# HackmodWear.net
KiCad netlist of a schematic drawn in EAGLE
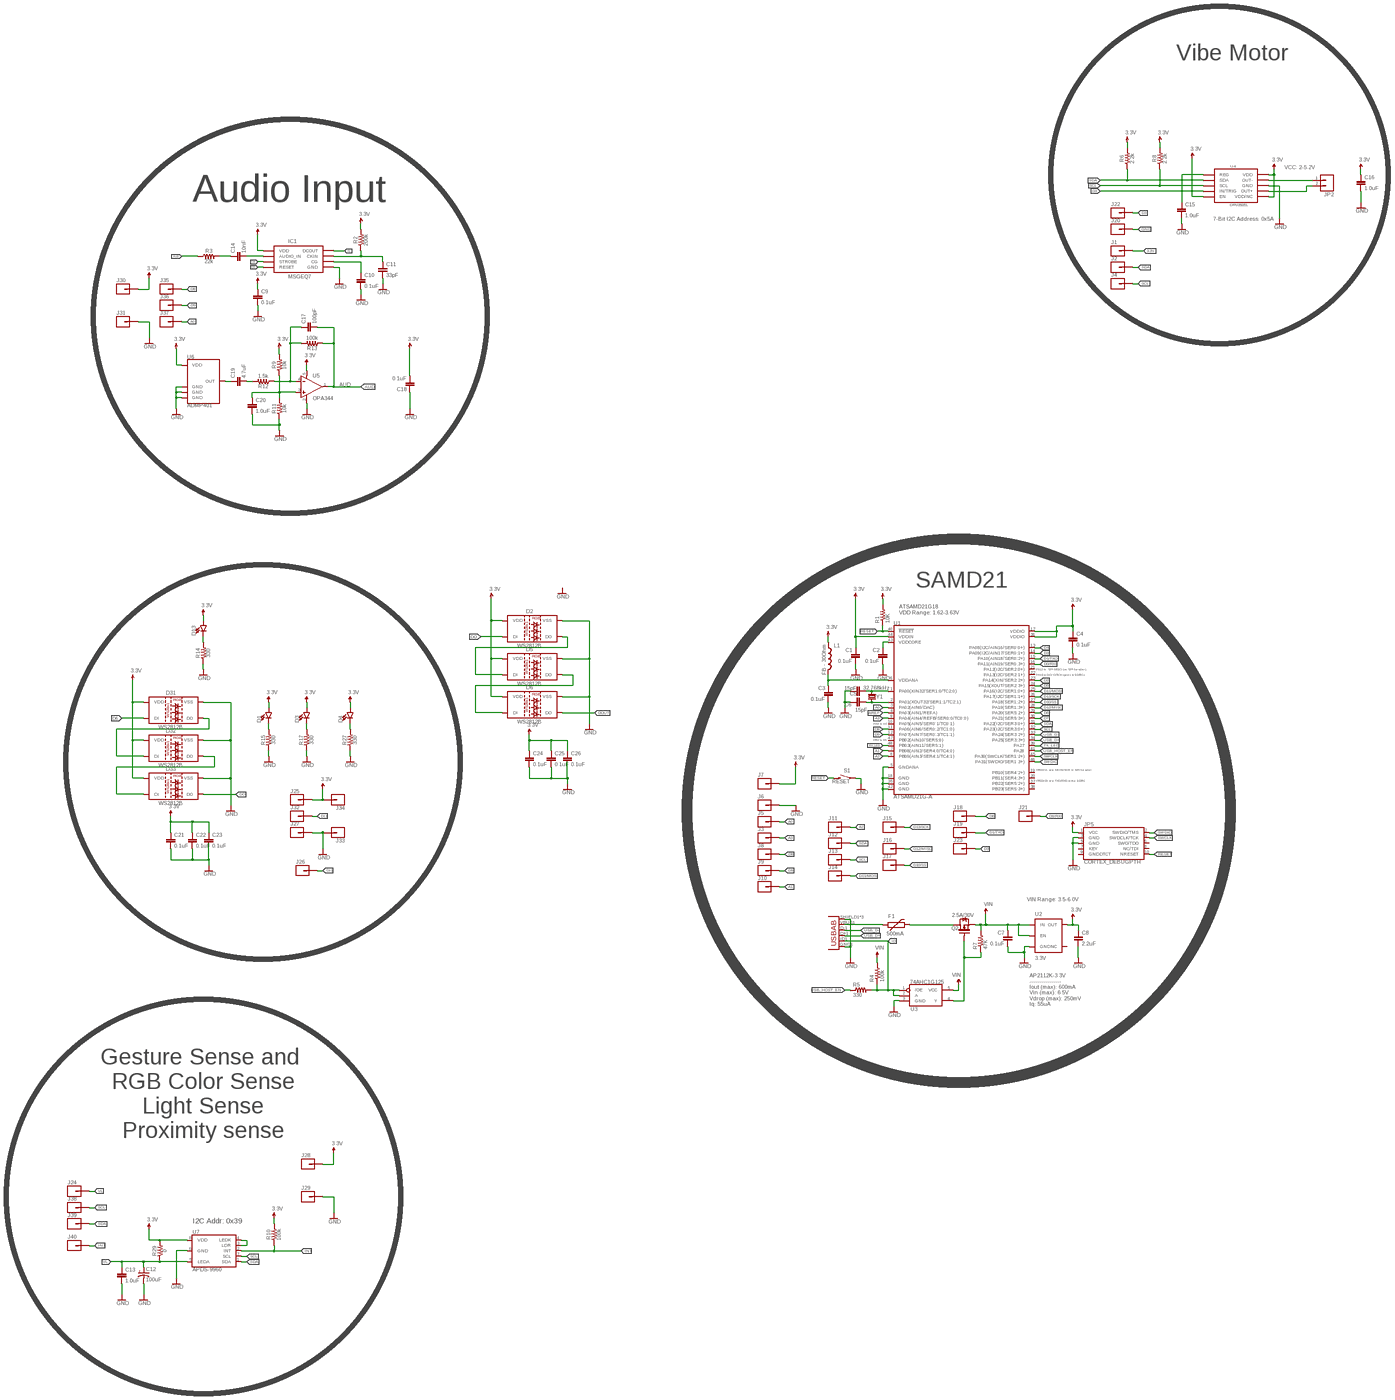
[diagram p0: schematic, sheet 1, overview]
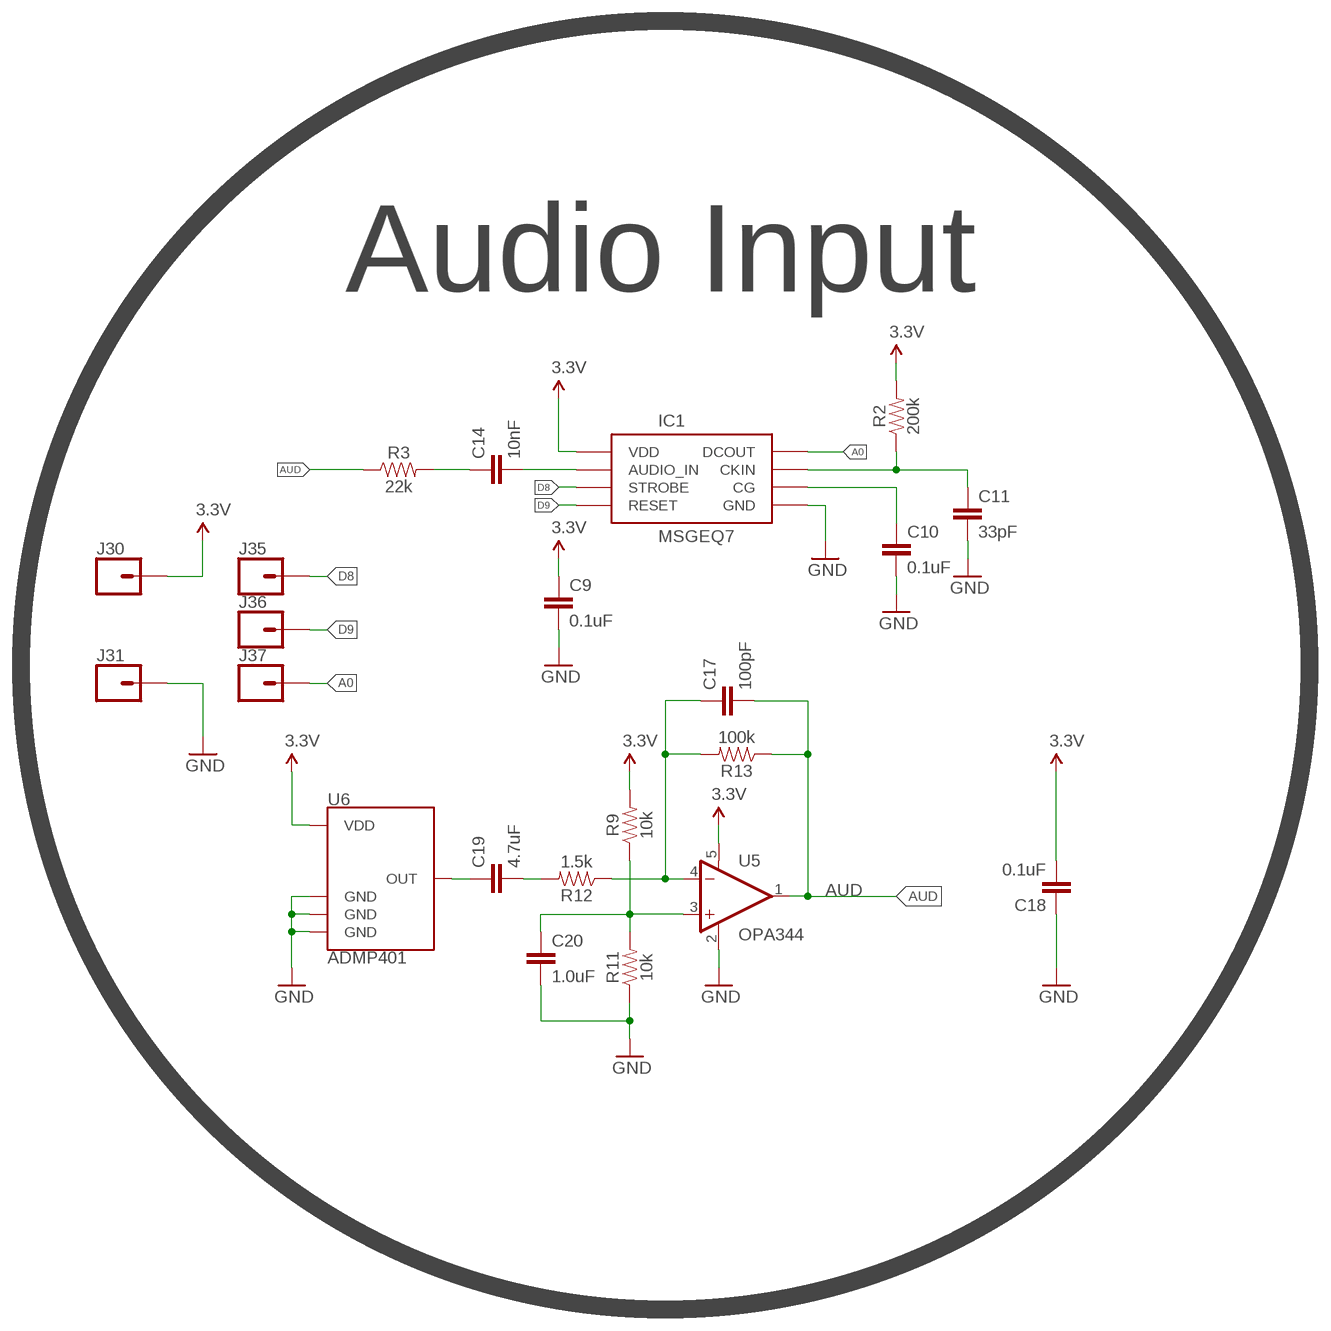
[diagram p1: schematic, sheet 1, part 1 of 4]
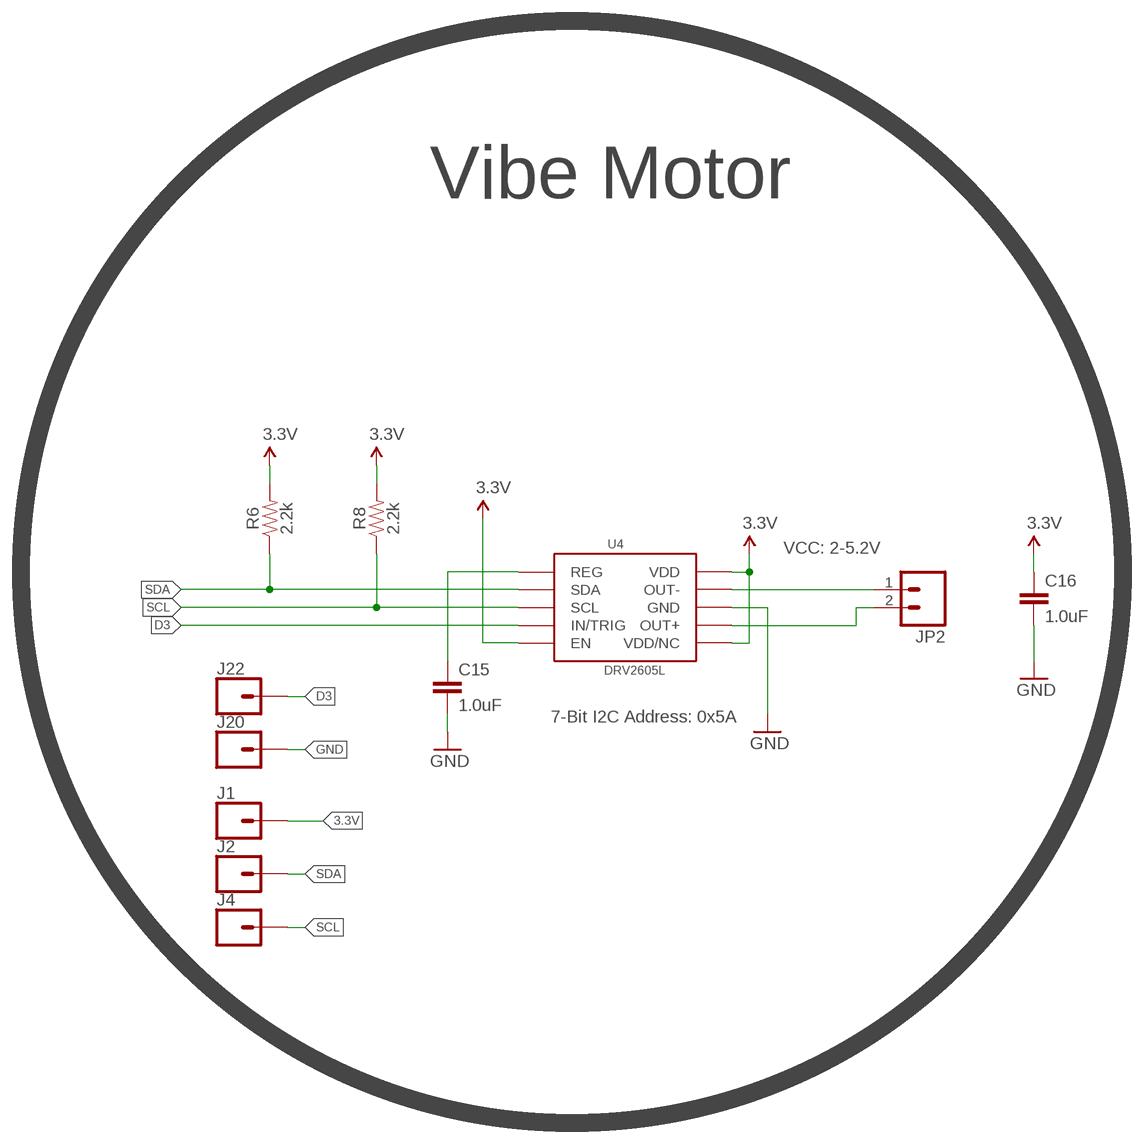
[diagram p2: schematic, sheet 1, part 2 of 4]
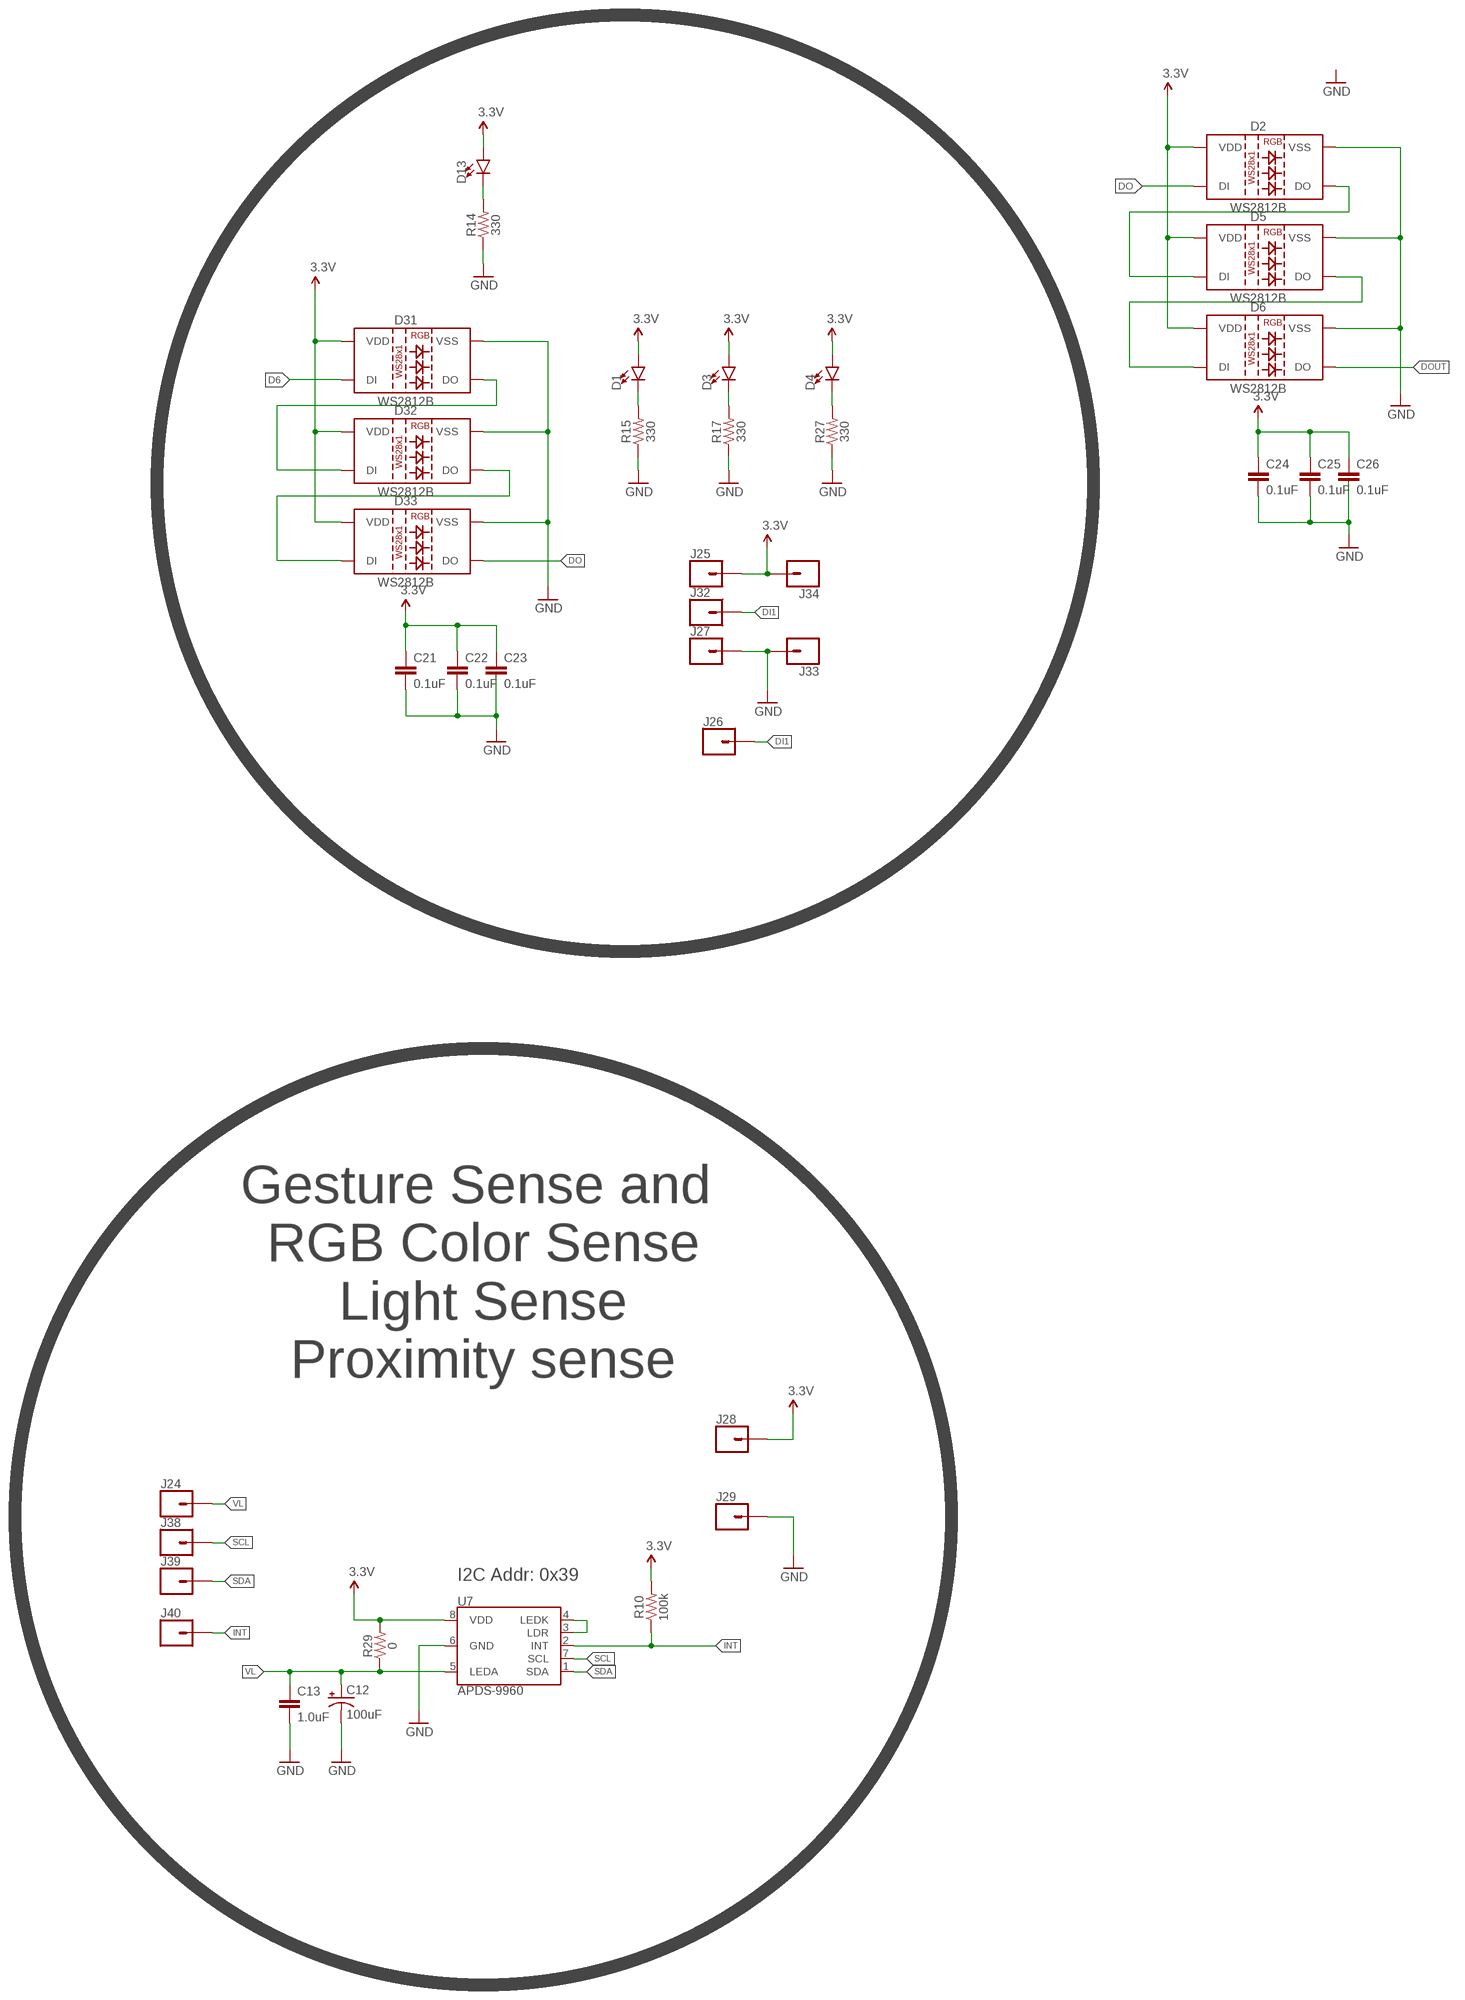
[diagram p3: schematic, sheet 1, part 3 of 4]
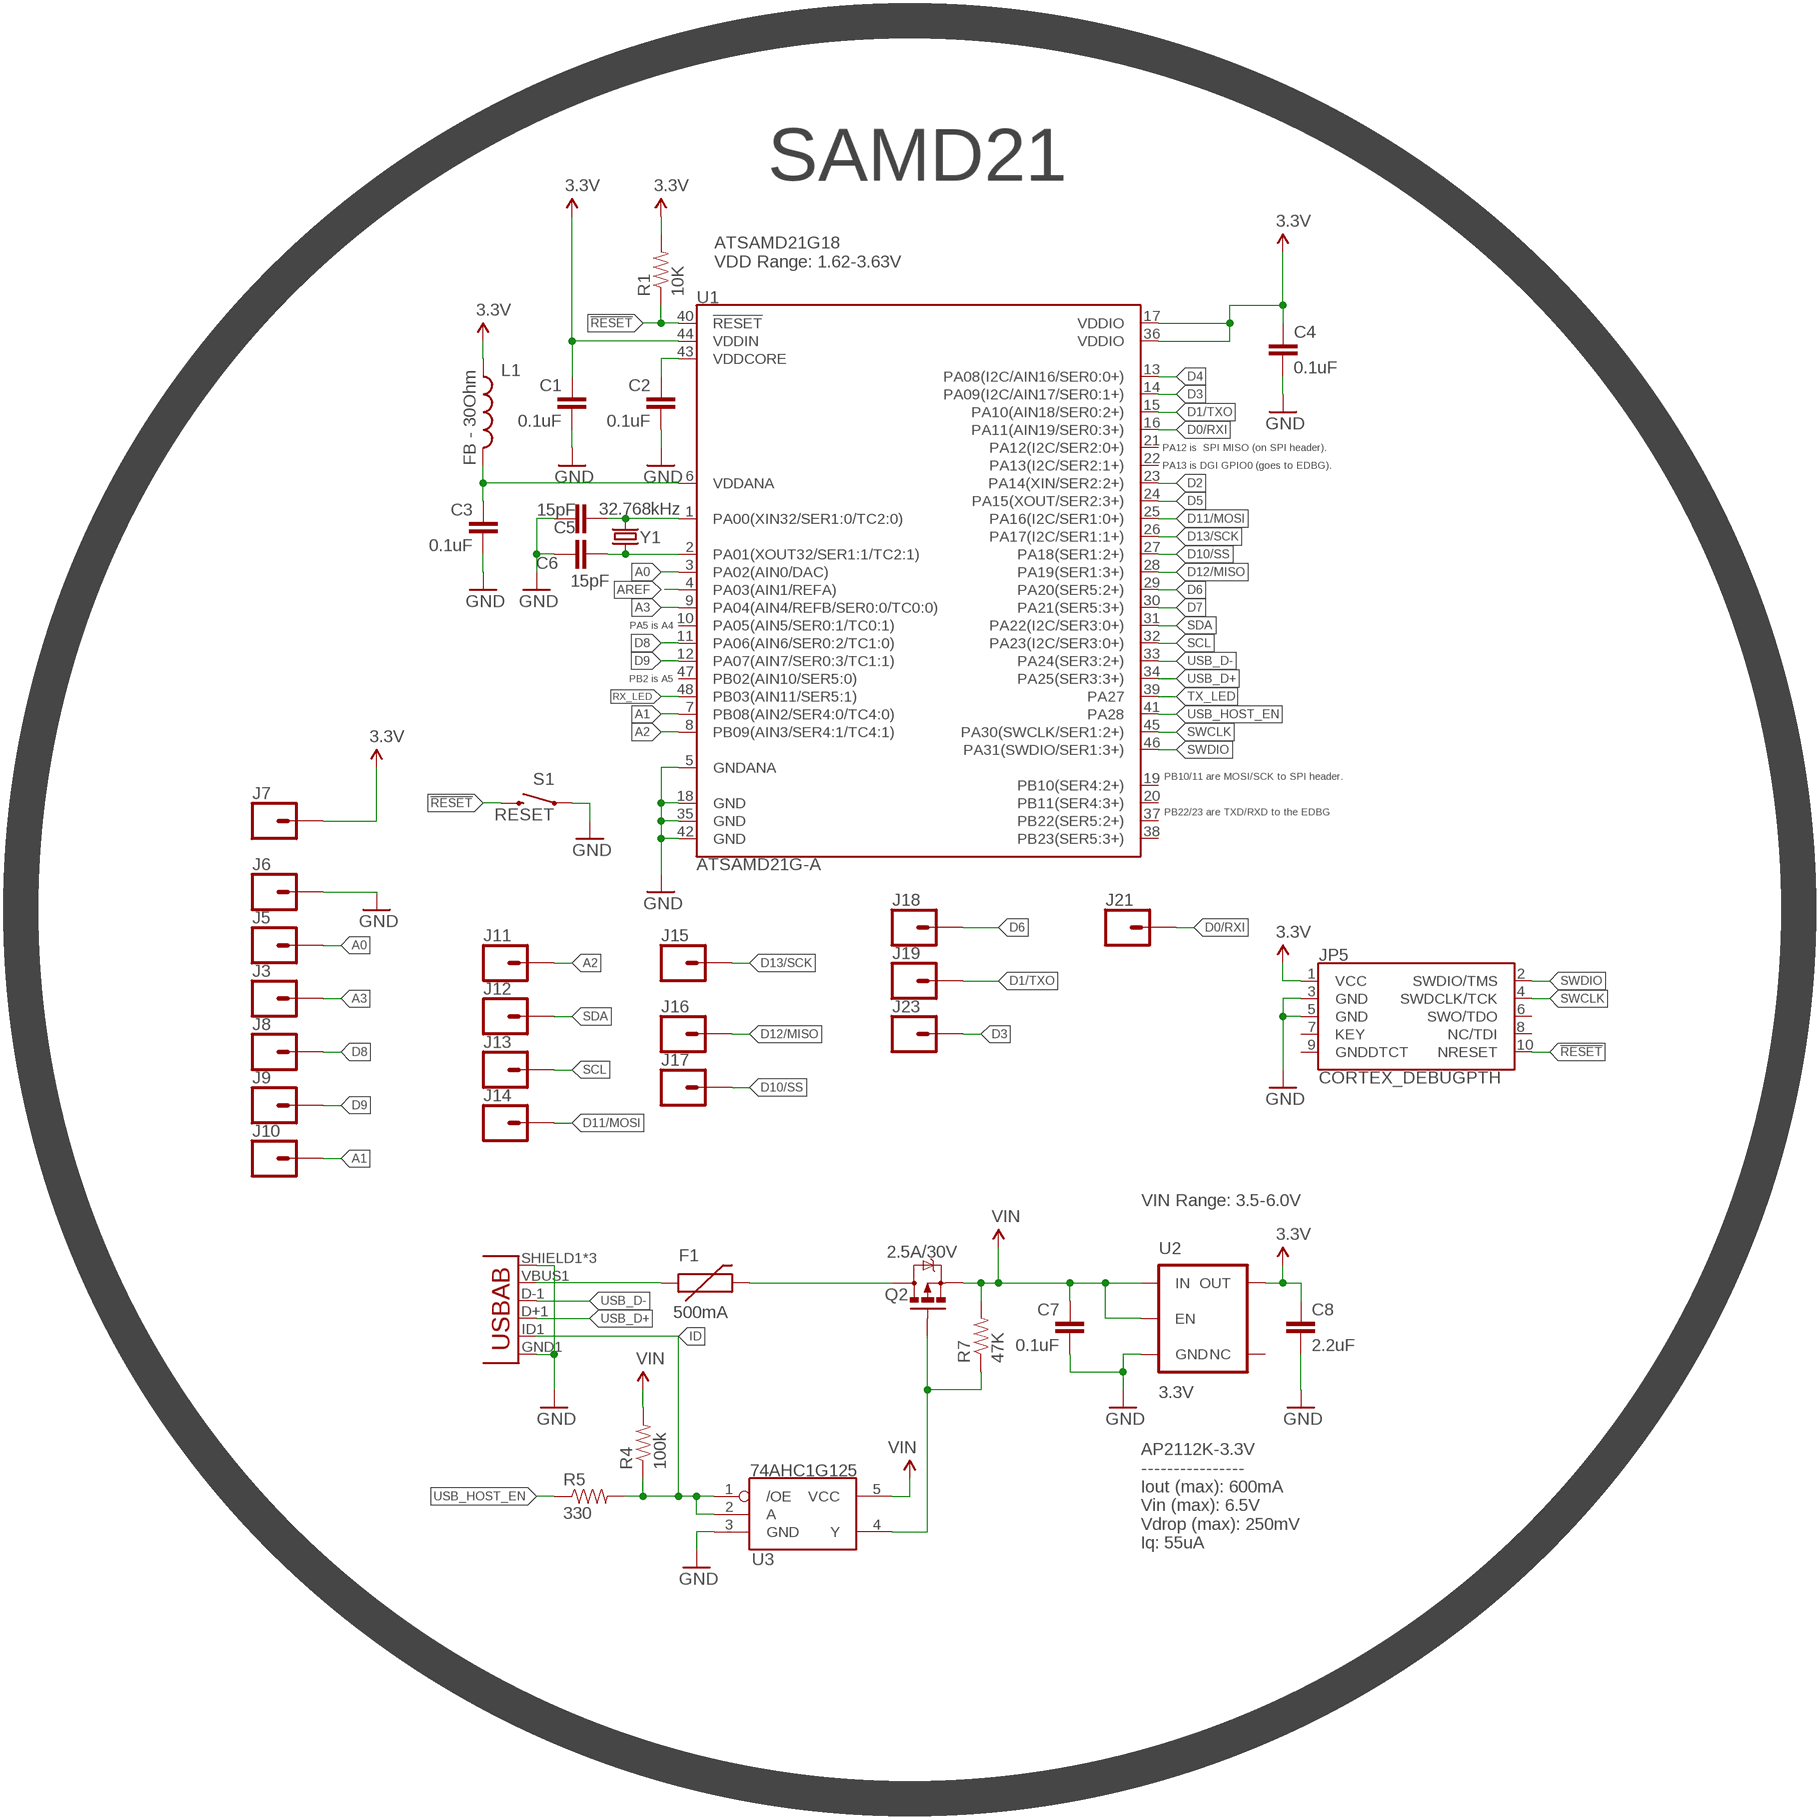
[diagram p4: schematic, sheet 1, part 4 of 4]

(export (version "E")
  (design (tool "Eeschema 10.0.6"))
  (components
    (comp (ref "C1")
      (value "0.1uF")
      (footprint "eagle-import:0603")
      (libsource (lib "eagle-import") (part "0.1UF-0603-25V-(+80/-20%)"))
    )
    (comp (ref "C2")
      (value "0.1uF")
      (footprint "eagle-import:0603")
      (libsource (lib "eagle-import") (part "0.1UF-0603-25V-(+80/-20%)"))
    )
    (comp (ref "C3")
      (value "0.1uF")
      (footprint "eagle-import:0603")
      (libsource (lib "eagle-import") (part "0.1UF-0603-25V-(+80/-20%)"))
    )
    (comp (ref "C4")
      (value "0.1uF")
      (footprint "eagle-import:0603")
      (libsource (lib "eagle-import") (part "0.1UF-0603-25V-(+80/-20%)"))
    )
    (comp (ref "C5")
      (value "15pF")
      (footprint "eagle-import:0603")
      (libsource (lib "eagle-import") (part "15PF-0603-50V-5%"))
    )
    (comp (ref "C6")
      (value "15pF")
      (footprint "eagle-import:0603")
      (libsource (lib "eagle-import") (part "15PF-0603-50V-5%"))
    )
    (comp (ref "C7")
      (value "0.1uF")
      (footprint "eagle-import:0603")
      (libsource (lib "eagle-import") (part "0.1UF-0603-25V-(+80/-20%)"))
    )
    (comp (ref "C8")
      (value "2.2uF")
      (footprint "eagle-import:0603-CAP")
      (libsource (lib "eagle-import") (part "2.2UF-10V-20%(0603)"))
    )
    (comp (ref "C9")
      (value "0.1uF")
      (footprint "eagle-import:0603")
      (libsource (lib "eagle-import") (part "0.1UF-0603-25V-(+80/-20%)"))
    )
    (comp (ref "C10")
      (value "0.1uF")
      (footprint "eagle-import:0603")
      (libsource (lib "eagle-import") (part "0.1UF-0603-25V-(+80/-20%)"))
    )
    (comp (ref "C11")
      (value "33pF")
      (footprint "eagle-import:0603")
      (libsource (lib "eagle-import") (part "33PF-0603-50V-5%"))
    )
    (comp (ref "C12")
      (value "100uF")
      (footprint "eagle-import:EIA7343")
      (libsource (lib "eagle-import") (part "100UF-POLAR-EIA7343-10V-10%(TANT)"))
    )
    (comp (ref "C13")
      (value "1.0uF")
      (footprint "eagle-import:0603")
      (libsource (lib "eagle-import") (part "1.0UF-0603-16V-10%"))
    )
    (comp (ref "C14")
      (value "10nF")
      (footprint "eagle-import:0603")
      (libsource (lib "eagle-import") (part "10NF-0603-50V-10%"))
    )
    (comp (ref "C15")
      (value "1.0uF")
      (footprint "eagle-import:0402-CAP")
      (libsource (lib "eagle-import") (part "1.0UF-16V-10%(0402)"))
    )
    (comp (ref "C16")
      (value "1.0uF")
      (footprint "eagle-import:0402-CAP")
      (libsource (lib "eagle-import") (part "1.0UF-16V-10%(0402)"))
    )
    (comp (ref "C17")
      (value "100pF")
      (footprint "eagle-import:0603")
      (libsource (lib "eagle-import") (part "100PF-0603-50V-5%"))
    )
    (comp (ref "C18")
      (value "0.1uF")
      (footprint "eagle-import:0603")
      (libsource (lib "eagle-import") (part "0.1UF-0603-25V-(+80/-20%)"))
    )
    (comp (ref "C19")
      (value "4.7uF")
      (footprint "eagle-import:0603")
      (libsource (lib "eagle-import") (part "4.7UF0603"))
    )
    (comp (ref "C20")
      (value "1.0uF")
      (footprint "eagle-import:0603")
      (libsource (lib "eagle-import") (part "1.0UF-0603-16V-10%"))
    )
    (comp (ref "C21")
      (value "0.1uF")
      (footprint "eagle-import:0603")
      (libsource (lib "eagle-import") (part "0.1UF-0603-25V-(+80/-20%)"))
    )
    (comp (ref "C22")
      (value "0.1uF")
      (footprint "eagle-import:0603")
      (libsource (lib "eagle-import") (part "0.1UF-0603-25V-(+80/-20%)"))
    )
    (comp (ref "C23")
      (value "0.1uF")
      (footprint "eagle-import:0603")
      (libsource (lib "eagle-import") (part "0.1UF-0603-25V-(+80/-20%)"))
    )
    (comp (ref "C24")
      (value "0.1uF")
      (footprint "eagle-import:0603")
      (libsource (lib "eagle-import") (part "0.1UF-0603-25V-(+80/-20%)"))
    )
    (comp (ref "C25")
      (value "0.1uF")
      (footprint "eagle-import:0603")
      (libsource (lib "eagle-import") (part "0.1UF-0603-25V-(+80/-20%)"))
    )
    (comp (ref "C26")
      (value "0.1uF")
      (footprint "eagle-import:0603")
      (libsource (lib "eagle-import") (part "0.1UF-0603-25V-(+80/-20%)"))
    )
    (comp (ref "D1")
      (value "LED1206")
      (footprint "eagle-import:LED-1206")
      (libsource (lib "eagle-import") (part "LED1206"))
    )
    (comp (ref "D2")
      (value "WS2812B")
      (footprint "eagle-import:WS2812B")
      (libsource (lib "eagle-import") (part "WS2812B"))
    )
    (comp (ref "D3")
      (value "LED1206")
      (footprint "eagle-import:LED-1206")
      (libsource (lib "eagle-import") (part "LED1206"))
    )
    (comp (ref "D4")
      (value "LED1206")
      (footprint "eagle-import:LED-1206")
      (libsource (lib "eagle-import") (part "LED1206"))
    )
    (comp (ref "D5")
      (value "WS2812B")
      (footprint "eagle-import:WS2812B")
      (libsource (lib "eagle-import") (part "WS2812B"))
    )
    (comp (ref "D6")
      (value "WS2812B")
      (footprint "eagle-import:WS2812B")
      (libsource (lib "eagle-import") (part "WS2812B"))
    )
    (comp (ref "D13")
      (value "LED1206")
      (footprint "eagle-import:LED-1206")
      (libsource (lib "eagle-import") (part "LED1206"))
    )
    (comp (ref "D31")
      (value "WS2812B")
      (footprint "eagle-import:WS2812B")
      (libsource (lib "eagle-import") (part "WS2812B"))
    )
    (comp (ref "D32")
      (value "WS2812B")
      (footprint "eagle-import:WS2812B")
      (libsource (lib "eagle-import") (part "WS2812B"))
    )
    (comp (ref "D33")
      (value "WS2812B")
      (footprint "eagle-import:WS2812B")
      (libsource (lib "eagle-import") (part "WS2812B"))
    )
    (comp (ref "F1")
      (value "500mA")
      (footprint "eagle-import:PTC-1206")
      (libsource (lib "eagle-import") (part "PTCSMD"))
    )
    (comp (ref "IC1")
      (value "MSGEQ7N")
      (footprint "eagle-import:SO08")
      (libsource (lib "eagle-import") (part "MSGEQ7SOIC"))
    )
    (comp (ref "J1")
      (value "CONN_01")
      (footprint "eagle-import:1X01")
      (libsource (lib "eagle-import") (part "CONN_01"))
    )
    (comp (ref "J2")
      (value "CONN_01")
      (footprint "eagle-import:1X01")
      (libsource (lib "eagle-import") (part "CONN_01"))
    )
    (comp (ref "J3")
      (value "CONN_01")
      (footprint "eagle-import:1X01")
      (libsource (lib "eagle-import") (part "CONN_01"))
    )
    (comp (ref "J4")
      (value "CONN_01")
      (footprint "eagle-import:1X01")
      (libsource (lib "eagle-import") (part "CONN_01"))
    )
    (comp (ref "J5")
      (value "CONN_01")
      (footprint "eagle-import:1X01")
      (libsource (lib "eagle-import") (part "CONN_01"))
    )
    (comp (ref "J6")
      (value "CONN_01")
      (footprint "eagle-import:1X01")
      (libsource (lib "eagle-import") (part "CONN_01"))
    )
    (comp (ref "J7")
      (value "CONN_01")
      (footprint "eagle-import:1X01")
      (libsource (lib "eagle-import") (part "CONN_01"))
    )
    (comp (ref "J8")
      (value "CONN_01")
      (footprint "eagle-import:1X01")
      (libsource (lib "eagle-import") (part "CONN_01"))
    )
    (comp (ref "J9")
      (value "CONN_01")
      (footprint "eagle-import:1X01")
      (libsource (lib "eagle-import") (part "CONN_01"))
    )
    (comp (ref "J10")
      (value "CONN_01")
      (footprint "eagle-import:1X01")
      (libsource (lib "eagle-import") (part "CONN_01"))
    )
    (comp (ref "J11")
      (value "CONN_01")
      (footprint "eagle-import:1X01")
      (libsource (lib "eagle-import") (part "CONN_01"))
    )
    (comp (ref "J12")
      (value "CONN_01")
      (footprint "eagle-import:1X01")
      (libsource (lib "eagle-import") (part "CONN_01"))
    )
    (comp (ref "J13")
      (value "CONN_01")
      (footprint "eagle-import:1X01")
      (libsource (lib "eagle-import") (part "CONN_01"))
    )
    (comp (ref "J14")
      (value "CONN_01")
      (footprint "eagle-import:1X01")
      (libsource (lib "eagle-import") (part "CONN_01"))
    )
    (comp (ref "J15")
      (value "CONN_01")
      (footprint "eagle-import:1X01")
      (libsource (lib "eagle-import") (part "CONN_01"))
    )
    (comp (ref "J16")
      (value "CONN_01")
      (footprint "eagle-import:1X01")
      (libsource (lib "eagle-import") (part "CONN_01"))
    )
    (comp (ref "J17")
      (value "CONN_01")
      (footprint "eagle-import:1X01")
      (libsource (lib "eagle-import") (part "CONN_01"))
    )
    (comp (ref "J18")
      (value "CONN_01")
      (footprint "eagle-import:1X01")
      (libsource (lib "eagle-import") (part "CONN_01"))
    )
    (comp (ref "J19")
      (value "CONN_01")
      (footprint "eagle-import:1X01")
      (libsource (lib "eagle-import") (part "CONN_01"))
    )
    (comp (ref "J20")
      (value "CONN_01")
      (footprint "eagle-import:1X01")
      (libsource (lib "eagle-import") (part "CONN_01"))
    )
    (comp (ref "J21")
      (value "CONN_01")
      (footprint "eagle-import:1X01")
      (libsource (lib "eagle-import") (part "CONN_01"))
    )
    (comp (ref "J22")
      (value "CONN_01")
      (footprint "eagle-import:1X01")
      (libsource (lib "eagle-import") (part "CONN_01"))
    )
    (comp (ref "J23")
      (value "CONN_01")
      (footprint "eagle-import:1X01")
      (libsource (lib "eagle-import") (part "CONN_01"))
    )
    (comp (ref "J24")
      (value "CONN_01")
      (footprint "eagle-import:1X01")
      (libsource (lib "eagle-import") (part "CONN_01"))
    )
    (comp (ref "J25")
      (value "CONN_01")
      (footprint "eagle-import:1X01")
      (libsource (lib "eagle-import") (part "CONN_01"))
    )
    (comp (ref "J26")
      (value "CONN_01")
      (footprint "eagle-import:1X01")
      (libsource (lib "eagle-import") (part "CONN_01"))
    )
    (comp (ref "J27")
      (value "CONN_01")
      (footprint "eagle-import:1X01")
      (libsource (lib "eagle-import") (part "CONN_01"))
    )
    (comp (ref "J28")
      (value "CONN_01")
      (footprint "eagle-import:1X01")
      (libsource (lib "eagle-import") (part "CONN_01"))
    )
    (comp (ref "J29")
      (value "CONN_01")
      (footprint "eagle-import:1X01")
      (libsource (lib "eagle-import") (part "CONN_01"))
    )
    (comp (ref "J30")
      (value "CONN_01")
      (footprint "eagle-import:1X01")
      (libsource (lib "eagle-import") (part "CONN_01"))
    )
    (comp (ref "J31")
      (value "CONN_01")
      (footprint "eagle-import:1X01")
      (libsource (lib "eagle-import") (part "CONN_01"))
    )
    (comp (ref "J32")
      (value "CONN_01")
      (footprint "eagle-import:1X01")
      (libsource (lib "eagle-import") (part "CONN_01"))
    )
    (comp (ref "J33")
      (value "CONN_01")
      (footprint "eagle-import:1X01")
      (libsource (lib "eagle-import") (part "CONN_01"))
    )
    (comp (ref "J34")
      (value "CONN_01")
      (footprint "eagle-import:1X01")
      (libsource (lib "eagle-import") (part "CONN_01"))
    )
    (comp (ref "J35")
      (value "CONN_01")
      (footprint "eagle-import:1X01")
      (libsource (lib "eagle-import") (part "CONN_01"))
    )
    (comp (ref "J36")
      (value "CONN_01")
      (footprint "eagle-import:1X01")
      (libsource (lib "eagle-import") (part "CONN_01"))
    )
    (comp (ref "J37")
      (value "CONN_01")
      (footprint "eagle-import:1X01")
      (libsource (lib "eagle-import") (part "CONN_01"))
    )
    (comp (ref "J38")
      (value "CONN_01")
      (footprint "eagle-import:1X01")
      (libsource (lib "eagle-import") (part "CONN_01"))
    )
    (comp (ref "J39")
      (value "CONN_01")
      (footprint "eagle-import:1X01")
      (libsource (lib "eagle-import") (part "CONN_01"))
    )
    (comp (ref "J40")
      (value "CONN_01")
      (footprint "eagle-import:1X01")
      (libsource (lib "eagle-import") (part "CONN_01"))
    )
    (comp (ref "JP2")
      (value "M02PTH")
      (footprint "eagle-import:1X02@1")
      (libsource (lib "eagle-import") (part "M02PTH"))
    )
    (comp (ref "JP3")
      (value "USB-ABCONN-11794")
      (footprint "eagle-import:USB-AB-MICRO-SMD_V03")
      (libsource (lib "eagle-import") (part "USB-ABCONN-11794"))
    )
    (comp (ref "JP5")
      (value "CORTEX_DEBUGPTH")
      (footprint "eagle-import:2X5-PTH-1.27MM")
      (libsource (lib "eagle-import") (part "CORTEX_DEBUGPTH"))
    )
    (comp (ref "L1")
      (value "FB - 30Ohm")
      (footprint "eagle-import:0603")
      (libsource (lib "eagle-import") (part "INDUCTOR0603"))
    )
    (comp (ref "Q2")
      (value "2.5A/30V")
      (footprint "eagle-import:SOT23-3")
      (libsource (lib "eagle-import") (part "MOSFET-PCHANNELDMG2307L"))
    )
    (comp (ref "R1")
      (value "10K")
      (footprint "eagle-import:0603-RES@1")
      (libsource (lib "eagle-import") (part "10KOHM-1/10W-1%(0603)0603"))
    )
    (comp (ref "R2")
      (value "200k")
      (footprint "eagle-import:0603")
      (libsource (lib "eagle-import") (part "200KOHM-0603-1/10W-1%"))
    )
    (comp (ref "R3")
      (value "22k")
      (footprint "eagle-import:0603")
      (libsource (lib "eagle-import") (part "22KOHM-0603-1/10W-1%"))
    )
    (comp (ref "R4")
      (value "100k")
      (footprint "eagle-import:0603-RES@1")
      (libsource (lib "eagle-import") (part "100KOHM-1/10W-1%(0603)"))
    )
    (comp (ref "R5")
      (value "330")
      (footprint "eagle-import:0603-RES@1")
      (libsource (lib "eagle-import") (part "330OHM1/10W1%(0603)"))
    )
    (comp (ref "R6")
      (value "2.2k")
      (footprint "eagle-import:0603")
      (libsource (lib "eagle-import") (part "2.2KOHM-0603-1/10W-1%"))
    )
    (comp (ref "R7")
      (value "47K")
      (footprint "eagle-import:0603-RES@1")
      (libsource (lib "eagle-import") (part "47KOHM1/10W1%(0603)"))
    )
    (comp (ref "R8")
      (value "2.2k")
      (footprint "eagle-import:0603")
      (libsource (lib "eagle-import") (part "2.2KOHM-0603-1/10W-1%"))
    )
    (comp (ref "R9")
      (value "10k")
      (footprint "eagle-import:0603")
      (libsource (lib "eagle-import") (part "10KOHM-0603-1/10W-1%"))
    )
    (comp (ref "R10")
      (value "100k")
      (footprint "eagle-import:0603")
      (libsource (lib "eagle-import") (part "100KOHM-0603-1/10W-1%"))
    )
    (comp (ref "R11")
      (value "10k")
      (footprint "eagle-import:0603")
      (libsource (lib "eagle-import") (part "10KOHM-0603-1/10W-1%"))
    )
    (comp (ref "R12")
      (value "1.5k")
      (footprint "eagle-import:0603")
      (libsource (lib "eagle-import") (part "1.5KOHM-0603-1/10W-1%"))
    )
    (comp (ref "R13")
      (value "100k")
      (footprint "eagle-import:0603")
      (libsource (lib "eagle-import") (part "100KOHM-0603-1/10W-1%"))
    )
    (comp (ref "R14")
      (value "330")
      (footprint "eagle-import:0603")
      (libsource (lib "eagle-import") (part "330OHM-0603-1/10W-1%"))
    )
    (comp (ref "R15")
      (value "330")
      (footprint "eagle-import:0603")
      (libsource (lib "eagle-import") (part "330OHM-0603-1/10W-1%"))
    )
    (comp (ref "R17")
      (value "330")
      (footprint "eagle-import:0603")
      (libsource (lib "eagle-import") (part "330OHM-0603-1/10W-1%"))
    )
    (comp (ref "R27")
      (value "330")
      (footprint "eagle-import:0603")
      (libsource (lib "eagle-import") (part "330OHM-0603-1/10W-1%"))
    )
    (comp (ref "R29")
      (value "0")
      (footprint "eagle-import:0603")
      (libsource (lib "eagle-import") (part "0OHM-0603-1/10W-5%"))
    )
    (comp (ref "S1")
      (value "RESET")
      (footprint "eagle-import:TACTILE_SWITCH_SMD_4.6X2.8MM")
      (libsource (lib "eagle-import") (part "SWITCH-MOMENTARY-2SMD-4.6X2.8MM"))
    )
    (comp (ref "U1")
      (value "ATSAMD21G-A")
      (footprint "eagle-import:TQFP-48")
      (libsource (lib "eagle-import") (part "ATSAMD21G-A"))
    )
    (comp (ref "U2")
      (value "3.3V")
      (footprint "eagle-import:SOT23-5")
      (libsource (lib "eagle-import") (part "V_REG_AP2112K-3.3V"))
    )
    (comp (ref "U3")
      (value "74AHC1G125")
      (footprint "eagle-import:SOT23-5")
      (libsource (lib "eagle-import") (part "74AHC1G125"))
    )
    (comp (ref "U4")
      (value "DRV2605L")
      (footprint "eagle-import:VSSOP-10")
      (libsource (lib "eagle-import") (part "DRV2605L"))
    )
    (comp (ref "U5")
      (value "OPA344")
      (footprint "eagle-import:SOT23-5")
      (libsource (lib "eagle-import") (part "OPA344"))
    )
    (comp (ref "U6")
      (value "ADMP401")
      (footprint "eagle-import:ADMP401")
      (libsource (lib "eagle-import") (part "ADMP401"))
    )
    (comp (ref "U7")
      (value "APDS-9960")
      (footprint "eagle-import:APDS-9960")
      (libsource (lib "eagle-import") (part "APDS-9960"))
    )
    (comp (ref "Y1")
      (value "32.768kHz")
      (footprint "eagle-import:CRYSTAL-SMD-3.2X1.5MM")
      (libsource (lib "eagle-import") (part "CRYSTAL3.2X1.5MM"))
    )
  )
  (nets
    (net (code "1") (name "/~{RESET}") (class "Default")
      (node (ref "JP5") (pin "10") (pinfunction "NRESET_10") (pintype "bidirectional"))
      (node (ref "R1") (pin "1") (pinfunction "1_1") (pintype "passive"))
      (node (ref "S1") (pin "3") (pinfunction "2_3") (pintype "passive"))
      (node (ref "S1") (pin "4") (pinfunction "2_4") (pintype "passive"))
      (node (ref "U1") (pin "40") (pinfunction "~{RESET}_40") (pintype "bidirectional"))
    )
    (net (code "2") (name "3.3V") (class "Default")
      (node (ref "C1") (pin "1") (pinfunction "1_1") (pintype "passive"))
      (node (ref "C16") (pin "1") (pinfunction "1_1") (pintype "passive"))
      (node (ref "C18") (pin "2") (pinfunction "2_2") (pintype "passive"))
      (node (ref "C21") (pin "1") (pinfunction "1_1") (pintype "passive"))
      (node (ref "C22") (pin "1") (pinfunction "1_1") (pintype "passive"))
      (node (ref "C23") (pin "1") (pinfunction "1_1") (pintype "passive"))
      (node (ref "C24") (pin "1") (pinfunction "1_1") (pintype "passive"))
      (node (ref "C25") (pin "1") (pinfunction "1_1") (pintype "passive"))
      (node (ref "C26") (pin "1") (pinfunction "1_1") (pintype "passive"))
      (node (ref "C4") (pin "1") (pinfunction "1_1") (pintype "passive"))
      (node (ref "C8") (pin "1") (pinfunction "1_1") (pintype "passive"))
      (node (ref "C9") (pin "1") (pinfunction "1_1") (pintype "passive"))
      (node (ref "D1") (pin "A") (pinfunction "A_A") (pintype "passive"))
      (node (ref "D13") (pin "A") (pinfunction "A_A") (pintype "passive"))
      (node (ref "D2") (pin "1") (pinfunction "VDD_1") (pintype "bidirectional"))
      (node (ref "D3") (pin "A") (pinfunction "A_A") (pintype "passive"))
      (node (ref "D31") (pin "1") (pinfunction "VDD_1") (pintype "bidirectional"))
      (node (ref "D32") (pin "1") (pinfunction "VDD_1") (pintype "bidirectional"))
      (node (ref "D33") (pin "1") (pinfunction "VDD_1") (pintype "bidirectional"))
      (node (ref "D4") (pin "A") (pinfunction "A_A") (pintype "passive"))
      (node (ref "D5") (pin "1") (pinfunction "VDD_1") (pintype "bidirectional"))
      (node (ref "D6") (pin "1") (pinfunction "VDD_1") (pintype "bidirectional"))
      (node (ref "IC1") (pin "1") (pinfunction "VDD_1") (pintype "input"))
      (node (ref "J1") (pin "P$1") (pinfunction "1_P$1") (pintype "passive"))
      (node (ref "J25") (pin "P$1") (pinfunction "1_P$1") (pintype "passive"))
      (node (ref "J28") (pin "P$1") (pinfunction "1_P$1") (pintype "passive"))
      (node (ref "J30") (pin "P$1") (pinfunction "1_P$1") (pintype "passive"))
      (node (ref "J34") (pin "P$1") (pinfunction "1_P$1") (pintype "passive"))
      (node (ref "J7") (pin "P$1") (pinfunction "1_P$1") (pintype "passive"))
      (node (ref "JP5") (pin "1") (pinfunction "VCC_1") (pintype "bidirectional"))
      (node (ref "L1") (pin "1") (pinfunction "1_1") (pintype "passive"))
      (node (ref "R1") (pin "2") (pinfunction "2_2") (pintype "passive"))
      (node (ref "R10") (pin "2") (pinfunction "2_2") (pintype "passive"))
      (node (ref "R2") (pin "2") (pinfunction "2_2") (pintype "passive"))
      (node (ref "R29") (pin "2") (pinfunction "2_2") (pintype "passive"))
      (node (ref "R6") (pin "2") (pinfunction "2_2") (pintype "passive"))
      (node (ref "R8") (pin "2") (pinfunction "2_2") (pintype "passive"))
      (node (ref "R9") (pin "2") (pinfunction "2_2") (pintype "passive"))
      (node (ref "U1") (pin "17") (pinfunction "VDDIO_17") (pintype "bidirectional"))
      (node (ref "U1") (pin "36") (pinfunction "VDDIO_36") (pintype "bidirectional"))
      (node (ref "U1") (pin "44") (pinfunction "VDDIN_44") (pintype "bidirectional"))
      (node (ref "U2") (pin "5") (pinfunction "OUT_5") (pintype "passive"))
      (node (ref "U4") (pin "P$10") (pinfunction "VDD_P$10") (pintype "bidirectional"))
      (node (ref "U4") (pin "P$5") (pinfunction "EN_P$5") (pintype "bidirectional"))
      (node (ref "U4") (pin "P$6") (pinfunction "VDD/NC_P$6") (pintype "bidirectional"))
      (node (ref "U5") (pin "5") (pinfunction "V+_5") (pintype "power_in"))
      (node (ref "U6") (pin "5") (pinfunction "VDD_5") (pintype "bidirectional"))
      (node (ref "U7") (pin "8") (pinfunction "VDD_8") (pintype "bidirectional"))
    )
    (net (code "3") (name "A0") (class "Default")
      (node (ref "IC1") (pin "3") (pinfunction "DCOUT_3") (pintype "bidirectional"))
      (node (ref "J37") (pin "P$1") (pinfunction "1_P$1") (pintype "passive"))
      (node (ref "J5") (pin "P$1") (pinfunction "1_P$1") (pintype "passive"))
      (node (ref "U1") (pin "3") (pinfunction "PA02(AIN0/DAC)_3") (pintype "bidirectional"))
    )
    (net (code "4") (name "A1") (class "Default")
      (node (ref "J10") (pin "P$1") (pinfunction "1_P$1") (pintype "passive"))
      (node (ref "U1") (pin "7") (pinfunction "PB08(AIN2/SER4:0/TC4:0)_7") (pintype "bidirectional"))
    )
    (net (code "5") (name "A2") (class "Default")
      (node (ref "J11") (pin "P$1") (pinfunction "1_P$1") (pintype "passive"))
      (node (ref "U1") (pin "8") (pinfunction "PB09(AIN3/SER4:1/TC4:1)_8") (pintype "bidirectional"))
    )
    (net (code "6") (name "A3") (class "Default")
      (node (ref "J3") (pin "P$1") (pinfunction "1_P$1") (pintype "passive"))
      (node (ref "U1") (pin "9") (pinfunction "PA04(AIN4/REFB/SER0:0/TC0:0)_9") (pintype "bidirectional"))
    )
    (net (code "7") (name "AREF") (class "Default")
      (node (ref "U1") (pin "4") (pinfunction "PA03(AIN1/REFA)_4") (pintype "bidirectional"))
    )
    (net (code "8") (name "AUD") (class "Default")
      (node (ref "C17") (pin "2") (pinfunction "2_2") (pintype "passive"))
      (node (ref "R13") (pin "1") (pinfunction "1_1") (pintype "passive"))
      (node (ref "R3") (pin "1") (pinfunction "1_1") (pintype "passive"))
      (node (ref "U5") (pin "1") (pinfunction "OUT_1") (pintype "output"))
    )
    (net (code "9") (name "D0{slash}RXI") (class "Default")
      (node (ref "J21") (pin "P$1") (pinfunction "1_P$1") (pintype "passive"))
      (node (ref "U1") (pin "16") (pinfunction "PA11(AIN19/SER0:3+)_16") (pintype "bidirectional"))
    )
    (net (code "10") (name "D1{slash}TXO") (class "Default")
      (node (ref "J19") (pin "P$1") (pinfunction "1_P$1") (pintype "passive"))
      (node (ref "U1") (pin "15") (pinfunction "PA10(AIN18/SER0:2+)_15") (pintype "bidirectional"))
    )
    (net (code "11") (name "D2") (class "Default")
      (node (ref "U1") (pin "23") (pinfunction "PA14(XIN/SER2:2+)_23") (pintype "bidirectional"))
    )
    (net (code "12") (name "D3") (class "Default")
      (node (ref "J22") (pin "P$1") (pinfunction "1_P$1") (pintype "passive"))
      (node (ref "J23") (pin "P$1") (pinfunction "1_P$1") (pintype "passive"))
      (node (ref "U1") (pin "14") (pinfunction "PA09(I2C/AIN17/SER0:1+)_14") (pintype "bidirectional"))
      (node (ref "U4") (pin "P$4") (pinfunction "IN/TRIG_P$4") (pintype "bidirectional"))
    )
    (net (code "13") (name "D4") (class "Default")
      (node (ref "U1") (pin "13") (pinfunction "PA08(I2C/AIN16/SER0:0+)_13") (pintype "bidirectional"))
    )
    (net (code "14") (name "D5") (class "Default")
      (node (ref "U1") (pin "24") (pinfunction "PA15(XOUT/SER2:3+)_24") (pintype "bidirectional"))
    )
    (net (code "15") (name "D6") (class "Default")
      (node (ref "D31") (pin "4") (pinfunction "DI_4") (pintype "bidirectional"))
      (node (ref "J18") (pin "P$1") (pinfunction "1_P$1") (pintype "passive"))
      (node (ref "U1") (pin "29") (pinfunction "PA20(SER5:2+)_29") (pintype "bidirectional"))
    )
    (net (code "16") (name "D7") (class "Default")
      (node (ref "U1") (pin "30") (pinfunction "PA21(SER5:3+)_30") (pintype "bidirectional"))
    )
    (net (code "17") (name "D8") (class "Default")
      (node (ref "IC1") (pin "4") (pinfunction "STROBE_4") (pintype "input"))
      (node (ref "J35") (pin "P$1") (pinfunction "1_P$1") (pintype "passive"))
      (node (ref "J8") (pin "P$1") (pinfunction "1_P$1") (pintype "passive"))
      (node (ref "U1") (pin "11") (pinfunction "PA06(AIN6/SER0:2/TC1:0)_11") (pintype "bidirectional"))
    )
    (net (code "18") (name "D9") (class "Default")
      (node (ref "IC1") (pin "7") (pinfunction "RESET_7") (pintype "input"))
      (node (ref "J36") (pin "P$1") (pinfunction "1_P$1") (pintype "passive"))
      (node (ref "J9") (pin "P$1") (pinfunction "1_P$1") (pintype "passive"))
      (node (ref "U1") (pin "12") (pinfunction "PA07(AIN7/SER0:3/TC1:1)_12") (pintype "bidirectional"))
    )
    (net (code "19") (name "D10{slash}SS") (class "Default")
      (node (ref "J17") (pin "P$1") (pinfunction "1_P$1") (pintype "passive"))
      (node (ref "U1") (pin "27") (pinfunction "PA18(SER1:2+)_27") (pintype "bidirectional"))
    )
    (net (code "20") (name "D11{slash}MOSI") (class "Default")
      (node (ref "J14") (pin "P$1") (pinfunction "1_P$1") (pintype "passive"))
      (node (ref "U1") (pin "25") (pinfunction "PA16(I2C/SER1:0+)_25") (pintype "bidirectional"))
    )
    (net (code "21") (name "D12{slash}MISO") (class "Default")
      (node (ref "J16") (pin "P$1") (pinfunction "1_P$1") (pintype "passive"))
      (node (ref "U1") (pin "28") (pinfunction "PA19(SER1:3+)_28") (pintype "bidirectional"))
    )
    (net (code "22") (name "D13{slash}SCK") (class "Default")
      (node (ref "J15") (pin "P$1") (pinfunction "1_P$1") (pintype "passive"))
      (node (ref "U1") (pin "26") (pinfunction "PA17(I2C/SER1:1+)_26") (pintype "bidirectional"))
    )
    (net (code "23") (name "DI1") (class "Default")
      (node (ref "J26") (pin "P$1") (pinfunction "1_P$1") (pintype "passive"))
      (node (ref "J32") (pin "P$1") (pinfunction "1_P$1") (pintype "passive"))
    )
    (net (code "24") (name "DO") (class "Default")
      (node (ref "D2") (pin "4") (pinfunction "DI_4") (pintype "bidirectional"))
      (node (ref "D33") (pin "2") (pinfunction "DO_2") (pintype "bidirectional"))
    )
    (net (code "25") (name "DOUT") (class "Default")
      (node (ref "D6") (pin "2") (pinfunction "DO_2") (pintype "bidirectional"))
    )
    (net (code "26") (name "GND") (class "Default")
      (node (ref "C1") (pin "2") (pinfunction "2_2") (pintype "passive"))
      (node (ref "C10") (pin "2") (pinfunction "2_2") (pintype "passive"))
      (node (ref "C11") (pin "2") (pinfunction "2_2") (pintype "passive"))
      (node (ref "C12") (pin "C") (pinfunction "-_C") (pintype "passive"))
      (node (ref "C13") (pin "2") (pinfunction "2_2") (pintype "passive"))
      (node (ref "C15") (pin "2") (pinfunction "2_2") (pintype "passive"))
      (node (ref "C16") (pin "2") (pinfunction "2_2") (pintype "passive"))
      (node (ref "C18") (pin "1") (pinfunction "1_1") (pintype "passive"))
      (node (ref "C2") (pin "2") (pinfunction "2_2") (pintype "passive"))
      (node (ref "C20") (pin "2") (pinfunction "2_2") (pintype "passive"))
      (node (ref "C21") (pin "2") (pinfunction "2_2") (pintype "passive"))
      (node (ref "C22") (pin "2") (pinfunction "2_2") (pintype "passive"))
      (node (ref "C23") (pin "2") (pinfunction "2_2") (pintype "passive"))
      (node (ref "C24") (pin "2") (pinfunction "2_2") (pintype "passive"))
      (node (ref "C25") (pin "2") (pinfunction "2_2") (pintype "passive"))
      (node (ref "C26") (pin "2") (pinfunction "2_2") (pintype "passive"))
      (node (ref "C3") (pin "2") (pinfunction "2_2") (pintype "passive"))
      (node (ref "C4") (pin "2") (pinfunction "2_2") (pintype "passive"))
      (node (ref "C5") (pin "1") (pinfunction "1_1") (pintype "passive"))
      (node (ref "C6") (pin "2") (pinfunction "2_2") (pintype "passive"))
      (node (ref "C7") (pin "2") (pinfunction "2_2") (pintype "passive"))
      (node (ref "C8") (pin "2") (pinfunction "2_2") (pintype "passive"))
      (node (ref "C9") (pin "2") (pinfunction "2_2") (pintype "passive"))
      (node (ref "D2") (pin "3") (pinfunction "VSS_3") (pintype "bidirectional"))
      (node (ref "D31") (pin "3") (pinfunction "VSS_3") (pintype "bidirectional"))
      (node (ref "D32") (pin "3") (pinfunction "VSS_3") (pintype "bidirectional"))
      (node (ref "D33") (pin "3") (pinfunction "VSS_3") (pintype "bidirectional"))
      (node (ref "D5") (pin "3") (pinfunction "VSS_3") (pintype "bidirectional"))
      (node (ref "D6") (pin "3") (pinfunction "VSS_3") (pintype "bidirectional"))
      (node (ref "IC1") (pin "2") (pinfunction "GND_2") (pintype "bidirectional"))
      (node (ref "J20") (pin "P$1") (pinfunction "1_P$1") (pintype "passive"))
      (node (ref "J27") (pin "P$1") (pinfunction "1_P$1") (pintype "passive"))
      (node (ref "J29") (pin "P$1") (pinfunction "1_P$1") (pintype "passive"))
      (node (ref "J31") (pin "P$1") (pinfunction "1_P$1") (pintype "passive"))
      (node (ref "J33") (pin "P$1") (pinfunction "1_P$1") (pintype "passive"))
      (node (ref "J6") (pin "P$1") (pinfunction "1_P$1") (pintype "passive"))
      (node (ref "JP3") (pin "GND1") (pinfunction "GND_GND1") (pintype "bidirectional"))
      (node (ref "JP3") (pin "SHIELD1") (pinfunction "SHIELD_SHIELD1") (pintype "bidirectional"))
      (node (ref "JP3") (pin "SHIELD2") (pinfunction "SHIELD_SHIELD2") (pintype "bidirectional"))
      (node (ref "JP3") (pin "SHIELD3") (pinfunction "SHIELD_SHIELD3") (pintype "bidirectional"))
      (node (ref "JP5") (pin "3") (pinfunction "GND_3") (pintype "bidirectional"))
      (node (ref "JP5") (pin "5") (pinfunction "GND_5") (pintype "bidirectional"))
      (node (ref "R11") (pin "1") (pinfunction "1_1") (pintype "passive"))
      (node (ref "R14") (pin "1") (pinfunction "1_1") (pintype "passive"))
      (node (ref "R15") (pin "1") (pinfunction "1_1") (pintype "passive"))
      (node (ref "R17") (pin "1") (pinfunction "1_1") (pintype "passive"))
      (node (ref "R27") (pin "1") (pinfunction "1_1") (pintype "passive"))
      (node (ref "S1") (pin "1") (pinfunction "1_1") (pintype "passive"))
      (node (ref "S1") (pin "2") (pinfunction "1_2") (pintype "passive"))
      (node (ref "U1") (pin "18") (pinfunction "GND_18") (pintype "bidirectional"))
      (node (ref "U1") (pin "35") (pinfunction "GND_35") (pintype "bidirectional"))
      (node (ref "U1") (pin "42") (pinfunction "GND_42") (pintype "bidirectional"))
      (node (ref "U1") (pin "5") (pinfunction "GNDANA_5") (pintype "bidirectional"))
      (node (ref "U2") (pin "2") (pinfunction "GND_2") (pintype "input"))
      (node (ref "U3") (pin "3") (pinfunction "GND_3") (pintype "bidirectional"))
      (node (ref "U4") (pin "P$8") (pinfunction "GND_P$8") (pintype "bidirectional"))
      (node (ref "U5") (pin "2") (pinfunction "V-_2") (pintype "power_in"))
      (node (ref "U6") (pin "2") (pinfunction "GND_2") (pintype "bidirectional"))
      (node (ref "U6") (pin "4") (pinfunction "GND_4") (pintype "bidirectional"))
      (node (ref "U6") (pin "6") (pinfunction "GND_6") (pintype "bidirectional"))
      (node (ref "U7") (pin "6") (pinfunction "GND_6") (pintype "bidirectional"))
    )
    (net (code "27") (name "ID") (class "Default")
      (node (ref "JP3") (pin "ID1") (pinfunction "USBID_ID1") (pintype "bidirectional"))
      (node (ref "R4") (pin "1") (pinfunction "1_1") (pintype "passive"))
      (node (ref "R5") (pin "2") (pinfunction "2_2") (pintype "passive"))
      (node (ref "U3") (pin "1") (pinfunction "/OE_1") (pintype "bidirectional"))
      (node (ref "U3") (pin "2") (pinfunction "A_2") (pintype "bidirectional"))
    )
    (net (code "28") (name "INT") (class "Default")
      (node (ref "J40") (pin "P$1") (pinfunction "1_P$1") (pintype "passive"))
      (node (ref "R10") (pin "1") (pinfunction "1_1") (pintype "passive"))
      (node (ref "U7") (pin "2") (pinfunction "INT_2") (pintype "bidirectional"))
    )
    (net (code "29") (name "Net-(C14-Pad1)") (class "Default")
      (node (ref "C14") (pin "1") (pinfunction "1_1") (pintype "passive"))
      (node (ref "R3") (pin "2") (pinfunction "2_2") (pintype "passive"))
    )
    (net (code "30") (name "Net-(C19-Pad2)") (class "Default")
      (node (ref "C19") (pin "2") (pinfunction "2_2") (pintype "passive"))
      (node (ref "R12") (pin "2") (pinfunction "2_2") (pintype "passive"))
    )
    (net (code "31") (name "Net-(D1-PadC)") (class "Default")
      (node (ref "D1") (pin "C") (pinfunction "C_C") (pintype "passive"))
      (node (ref "R15") (pin "2") (pinfunction "2_2") (pintype "passive"))
    )
    (net (code "32") (name "Net-(D2-DO)") (class "Default")
      (node (ref "D2") (pin "2") (pinfunction "DO_2") (pintype "bidirectional"))
      (node (ref "D5") (pin "4") (pinfunction "DI_4") (pintype "bidirectional"))
    )
    (net (code "33") (name "Net-(D3-PadC)") (class "Default")
      (node (ref "D3") (pin "C") (pinfunction "C_C") (pintype "passive"))
      (node (ref "R17") (pin "2") (pinfunction "2_2") (pintype "passive"))
    )
    (net (code "34") (name "Net-(D4-PadC)") (class "Default")
      (node (ref "D4") (pin "C") (pinfunction "C_C") (pintype "passive"))
      (node (ref "R27") (pin "2") (pinfunction "2_2") (pintype "passive"))
    )
    (net (code "35") (name "Net-(D5-DO)") (class "Default")
      (node (ref "D5") (pin "2") (pinfunction "DO_2") (pintype "bidirectional"))
      (node (ref "D6") (pin "4") (pinfunction "DI_4") (pintype "bidirectional"))
    )
    (net (code "36") (name "Net-(D13-PadC)") (class "Default")
      (node (ref "D13") (pin "C") (pinfunction "C_C") (pintype "passive"))
      (node (ref "R14") (pin "2") (pinfunction "2_2") (pintype "passive"))
    )
    (net (code "37") (name "Net-(D31-DO)") (class "Default")
      (node (ref "D31") (pin "2") (pinfunction "DO_2") (pintype "bidirectional"))
      (node (ref "D32") (pin "4") (pinfunction "DI_4") (pintype "bidirectional"))
    )
    (net (code "38") (name "Net-(D32-DO)") (class "Default")
      (node (ref "D32") (pin "2") (pinfunction "DO_2") (pintype "bidirectional"))
      (node (ref "D33") (pin "4") (pinfunction "DI_4") (pintype "bidirectional"))
    )
    (net (code "39") (name "Net-(IC1-AUDIO_IN)") (class "Default")
      (node (ref "C14") (pin "2") (pinfunction "2_2") (pintype "passive"))
      (node (ref "IC1") (pin "5") (pinfunction "AUDIO_IN_5") (pintype "input"))
    )
    (net (code "40") (name "Net-(IC1-CG)") (class "Default")
      (node (ref "C10") (pin "1") (pinfunction "1_1") (pintype "passive"))
      (node (ref "IC1") (pin "6") (pinfunction "CG_6") (pintype "bidirectional"))
    )
    (net (code "41") (name "Net-(IC1-CKIN)") (class "Default")
      (node (ref "C11") (pin "1") (pinfunction "1_1") (pintype "passive"))
      (node (ref "IC1") (pin "8") (pinfunction "CKIN_8") (pintype "bidirectional"))
      (node (ref "R2") (pin "1") (pinfunction "1_1") (pintype "passive"))
    )
    (net (code "42") (name "Net-(JP3-VBUS)") (class "Default")
      (node (ref "F1") (pin "1") (pinfunction "1_1") (pintype "bidirectional"))
      (node (ref "JP3") (pin "VBUS1") (pinfunction "VBUS_VBUS1") (pintype "bidirectional"))
    )
    (net (code "43") (name "Net-(Q2-D)") (class "Default")
      (node (ref "F1") (pin "2") (pinfunction "2_2") (pintype "bidirectional"))
      (node (ref "Q2") (pin "3") (pinfunction "D_3") (pintype "passive"))
    )
    (net (code "44") (name "Net-(Q2-G)") (class "Default")
      (node (ref "Q2") (pin "1") (pinfunction "G_1") (pintype "passive"))
      (node (ref "R7") (pin "1") (pinfunction "1_1") (pintype "passive"))
      (node (ref "U3") (pin "4") (pinfunction "Y_4") (pintype "bidirectional"))
    )
    (net (code "45") (name "Net-(U1-PA00(XIN32{slash}SER1:0{slash}TC2:0))") (class "Default")
      (node (ref "C5") (pin "2") (pinfunction "2_2") (pintype "passive"))
      (node (ref "U1") (pin "1") (pinfunction "PA00(XIN32/SER1:0/TC2:0)_1") (pintype "bidirectional"))
      (node (ref "Y1") (pin "P$2") (pinfunction "2_P$2") (pintype "passive"))
    )
    (net (code "46") (name "Net-(U1-PA01(XOUT32{slash}SER1:1{slash}TC2:1))") (class "Default")
      (node (ref "C6") (pin "1") (pinfunction "1_1") (pintype "passive"))
      (node (ref "U1") (pin "2") (pinfunction "PA01(XOUT32/SER1:1/TC2:1)_2") (pintype "bidirectional"))
      (node (ref "Y1") (pin "P$1") (pinfunction "1_P$1") (pintype "passive"))
    )
    (net (code "47") (name "Net-(U1-VDDANA)") (class "Default")
      (node (ref "C3") (pin "1") (pinfunction "1_1") (pintype "passive"))
      (node (ref "L1") (pin "2") (pinfunction "2_2") (pintype "passive"))
      (node (ref "U1") (pin "6") (pinfunction "VDDANA_6") (pintype "bidirectional"))
    )
    (net (code "48") (name "Net-(U1-VDDCORE)") (class "Default")
      (node (ref "C2") (pin "1") (pinfunction "1_1") (pintype "passive"))
      (node (ref "U1") (pin "43") (pinfunction "VDDCORE_43") (pintype "bidirectional"))
    )
    (net (code "49") (name "Net-(U4-OUT+)") (class "Default")
      (node (ref "JP2") (pin "2") (pinfunction "2_2") (pintype "passive"))
      (node (ref "U4") (pin "P$7") (pinfunction "OUT+_P$7") (pintype "bidirectional"))
    )
    (net (code "50") (name "Net-(U4-OUT-)") (class "Default")
      (node (ref "JP2") (pin "1") (pinfunction "1_1") (pintype "passive"))
      (node (ref "U4") (pin "P$9") (pinfunction "OUT-_P$9") (pintype "bidirectional"))
    )
    (net (code "51") (name "Net-(U4-REG)") (class "Default")
      (node (ref "C15") (pin "1") (pinfunction "1_1") (pintype "passive"))
      (node (ref "U4") (pin "P$1") (pinfunction "REG_P$1") (pintype "bidirectional"))
    )
    (net (code "52") (name "Net-(U5-+IN)") (class "Default")
      (node (ref "C20") (pin "1") (pinfunction "1_1") (pintype "passive"))
      (node (ref "R11") (pin "2") (pinfunction "2_2") (pintype "passive"))
      (node (ref "R9") (pin "1") (pinfunction "1_1") (pintype "passive"))
      (node (ref "U5") (pin "3") (pinfunction "+IN_3") (pintype "input"))
    )
    (net (code "53") (name "Net-(U5--IN)") (class "Default")
      (node (ref "C17") (pin "1") (pinfunction "1_1") (pintype "passive"))
      (node (ref "R12") (pin "1") (pinfunction "1_1") (pintype "passive"))
      (node (ref "R13") (pin "2") (pinfunction "2_2") (pintype "passive"))
      (node (ref "U5") (pin "4") (pinfunction "-IN_4") (pintype "input"))
    )
    (net (code "54") (name "Net-(U6-OUT)") (class "Default")
      (node (ref "C19") (pin "1") (pinfunction "1_1") (pintype "passive"))
      (node (ref "U6") (pin "1") (pinfunction "OUT_1") (pintype "bidirectional"))
    )
    (net (code "55") (name "Net-(U7-LDR)") (class "Default")
      (node (ref "U7") (pin "3") (pinfunction "LDR_3") (pintype "bidirectional"))
      (node (ref "U7") (pin "4") (pinfunction "LEDK_4") (pintype "bidirectional"))
    )
    (net (code "56") (name "RX_LED") (class "Default")
      (node (ref "U1") (pin "48") (pinfunction "PB03(AIN11/SER5:1)_48") (pintype "bidirectional"))
    )
    (net (code "57") (name "SCL") (class "Default")
      (node (ref "J13") (pin "P$1") (pinfunction "1_P$1") (pintype "passive"))
      (node (ref "J38") (pin "P$1") (pinfunction "1_P$1") (pintype "passive"))
      (node (ref "J4") (pin "P$1") (pinfunction "1_P$1") (pintype "passive"))
      (node (ref "R8") (pin "1") (pinfunction "1_1") (pintype "passive"))
      (node (ref "U1") (pin "32") (pinfunction "PA23(I2C/SER3:0+)_32") (pintype "bidirectional"))
      (node (ref "U4") (pin "P$2") (pinfunction "SCL_P$2") (pintype "bidirectional"))
      (node (ref "U7") (pin "7") (pinfunction "SCL_7") (pintype "bidirectional"))
    )
    (net (code "58") (name "SDA") (class "Default")
      (node (ref "J12") (pin "P$1") (pinfunction "1_P$1") (pintype "passive"))
      (node (ref "J2") (pin "P$1") (pinfunction "1_P$1") (pintype "passive"))
      (node (ref "J39") (pin "P$1") (pinfunction "1_P$1") (pintype "passive"))
      (node (ref "R6") (pin "1") (pinfunction "1_1") (pintype "passive"))
      (node (ref "U1") (pin "31") (pinfunction "PA22(I2C/SER3:0+)_31") (pintype "bidirectional"))
      (node (ref "U4") (pin "P$3") (pinfunction "SDA_P$3") (pintype "bidirectional"))
      (node (ref "U7") (pin "1") (pinfunction "SDA_1") (pintype "bidirectional"))
    )
    (net (code "59") (name "SWCLK") (class "Default")
      (node (ref "JP5") (pin "4") (pinfunction "SWDCLK/TCK_4") (pintype "bidirectional"))
      (node (ref "U1") (pin "45") (pinfunction "PA30(SWCLK/SER1:2+)_45") (pintype "bidirectional"))
    )
    (net (code "60") (name "SWDIO") (class "Default")
      (node (ref "JP5") (pin "2") (pinfunction "SWDIO/TMS_2") (pintype "bidirectional"))
      (node (ref "U1") (pin "46") (pinfunction "PA31(SWDIO/SER1:3+)_46") (pintype "bidirectional"))
    )
    (net (code "61") (name "TX_LED") (class "Default")
      (node (ref "U1") (pin "39") (pinfunction "PA27_39") (pintype "bidirectional"))
    )
    (net (code "62") (name "USB_D+") (class "Default")
      (node (ref "JP3") (pin "D+1") (pinfunction "D+_D+1") (pintype "bidirectional"))
      (node (ref "U1") (pin "34") (pinfunction "PA25(SER3:3+)_34") (pintype "bidirectional"))
    )
    (net (code "63") (name "USB_D-") (class "Default")
      (node (ref "JP3") (pin "D-1") (pinfunction "D-_D-1") (pintype "bidirectional"))
      (node (ref "U1") (pin "33") (pinfunction "PA24(SER3:2+)_33") (pintype "bidirectional"))
    )
    (net (code "64") (name "USB_HOST_EN") (class "Default")
      (node (ref "R5") (pin "1") (pinfunction "1_1") (pintype "passive"))
      (node (ref "U1") (pin "41") (pinfunction "PA28_41") (pintype "bidirectional"))
    )
    (net (code "65") (name "VIN") (class "Default")
      (node (ref "C7") (pin "1") (pinfunction "1_1") (pintype "passive"))
      (node (ref "Q2") (pin "2") (pinfunction "S_2") (pintype "passive"))
      (node (ref "R4") (pin "2") (pinfunction "2_2") (pintype "passive"))
      (node (ref "R7") (pin "2") (pinfunction "2_2") (pintype "passive"))
      (node (ref "U2") (pin "1") (pinfunction "IN_1") (pintype "input"))
      (node (ref "U2") (pin "3") (pinfunction "EN_3") (pintype "input"))
      (node (ref "U3") (pin "5") (pinfunction "VCC_5") (pintype "bidirectional"))
    )
    (net (code "66") (name "VL") (class "Default")
      (node (ref "C12") (pin "A") (pinfunction "+_A") (pintype "passive"))
      (node (ref "C13") (pin "1") (pinfunction "1_1") (pintype "passive"))
      (node (ref "J24") (pin "P$1") (pinfunction "1_P$1") (pintype "passive"))
      (node (ref "R29") (pin "1") (pinfunction "1_1") (pintype "passive"))
      (node (ref "U7") (pin "5") (pinfunction "LEDA_5") (pintype "bidirectional"))
    )
    (net (code "67") (name "unconnected-(JP5-GNDDTCT-Pad9)") (class "Default")
      (node (ref "JP5") (pin "9") (pinfunction "GNDDTCT_9") (pintype "bidirectional"))
    )
    (net (code "68") (name "unconnected-(JP5-KEY-Pad7)") (class "Default")
      (node (ref "JP5") (pin "7") (pinfunction "KEY_7") (pintype "bidirectional"))
    )
    (net (code "69") (name "unconnected-(JP5-NC{slash}TDI-Pad8)") (class "Default")
      (node (ref "JP5") (pin "8") (pinfunction "NC/TDI_8") (pintype "bidirectional"))
    )
    (net (code "70") (name "unconnected-(JP5-SWO{slash}TDO-Pad6)") (class "Default")
      (node (ref "JP5") (pin "6") (pinfunction "SWO/TDO_6") (pintype "bidirectional"))
    )
    (net (code "71") (name "unconnected-(U1-PA05(AIN5{slash}SER0:1{slash}TC0:1)-Pad10)") (class "Default")
      (node (ref "U1") (pin "10") (pinfunction "PA05(AIN5/SER0:1/TC0:1)_10") (pintype "bidirectional"))
    )
    (net (code "72") (name "unconnected-(U1-PA12(I2C{slash}SER2:0+)-Pad21)") (class "Default")
      (node (ref "U1") (pin "21") (pinfunction "PA12(I2C/SER2:0+)_21") (pintype "bidirectional"))
    )
    (net (code "73") (name "unconnected-(U1-PA13(I2C{slash}SER2:1+)-Pad22)") (class "Default")
      (node (ref "U1") (pin "22") (pinfunction "PA13(I2C/SER2:1+)_22") (pintype "bidirectional"))
    )
    (net (code "74") (name "unconnected-(U1-PB02(AIN10{slash}SER5:0)-Pad47)") (class "Default")
      (node (ref "U1") (pin "47") (pinfunction "PB02(AIN10/SER5:0)_47") (pintype "bidirectional"))
    )
    (net (code "75") (name "unconnected-(U1-PB10(SER4:2+)-Pad19)") (class "Default")
      (node (ref "U1") (pin "19") (pinfunction "PB10(SER4:2+)_19") (pintype "bidirectional"))
    )
    (net (code "76") (name "unconnected-(U1-PB11(SER4:3+)-Pad20)") (class "Default")
      (node (ref "U1") (pin "20") (pinfunction "PB11(SER4:3+)_20") (pintype "bidirectional"))
    )
    (net (code "77") (name "unconnected-(U1-PB22(SER5:2+)-Pad37)") (class "Default")
      (node (ref "U1") (pin "37") (pinfunction "PB22(SER5:2+)_37") (pintype "bidirectional"))
    )
    (net (code "78") (name "unconnected-(U1-PB23(SER5:3+)-Pad38)") (class "Default")
      (node (ref "U1") (pin "38") (pinfunction "PB23(SER5:3+)_38") (pintype "bidirectional"))
    )
    (net (code "79") (name "unconnected-(U2-NC-Pad4)") (class "Default")
      (node (ref "U2") (pin "4") (pinfunction "NC_4") (pintype "input"))
    )
  )
)
